# S1-MAIN-20201205.net
KiCad netlist of a schematic drawn in Altium Designer
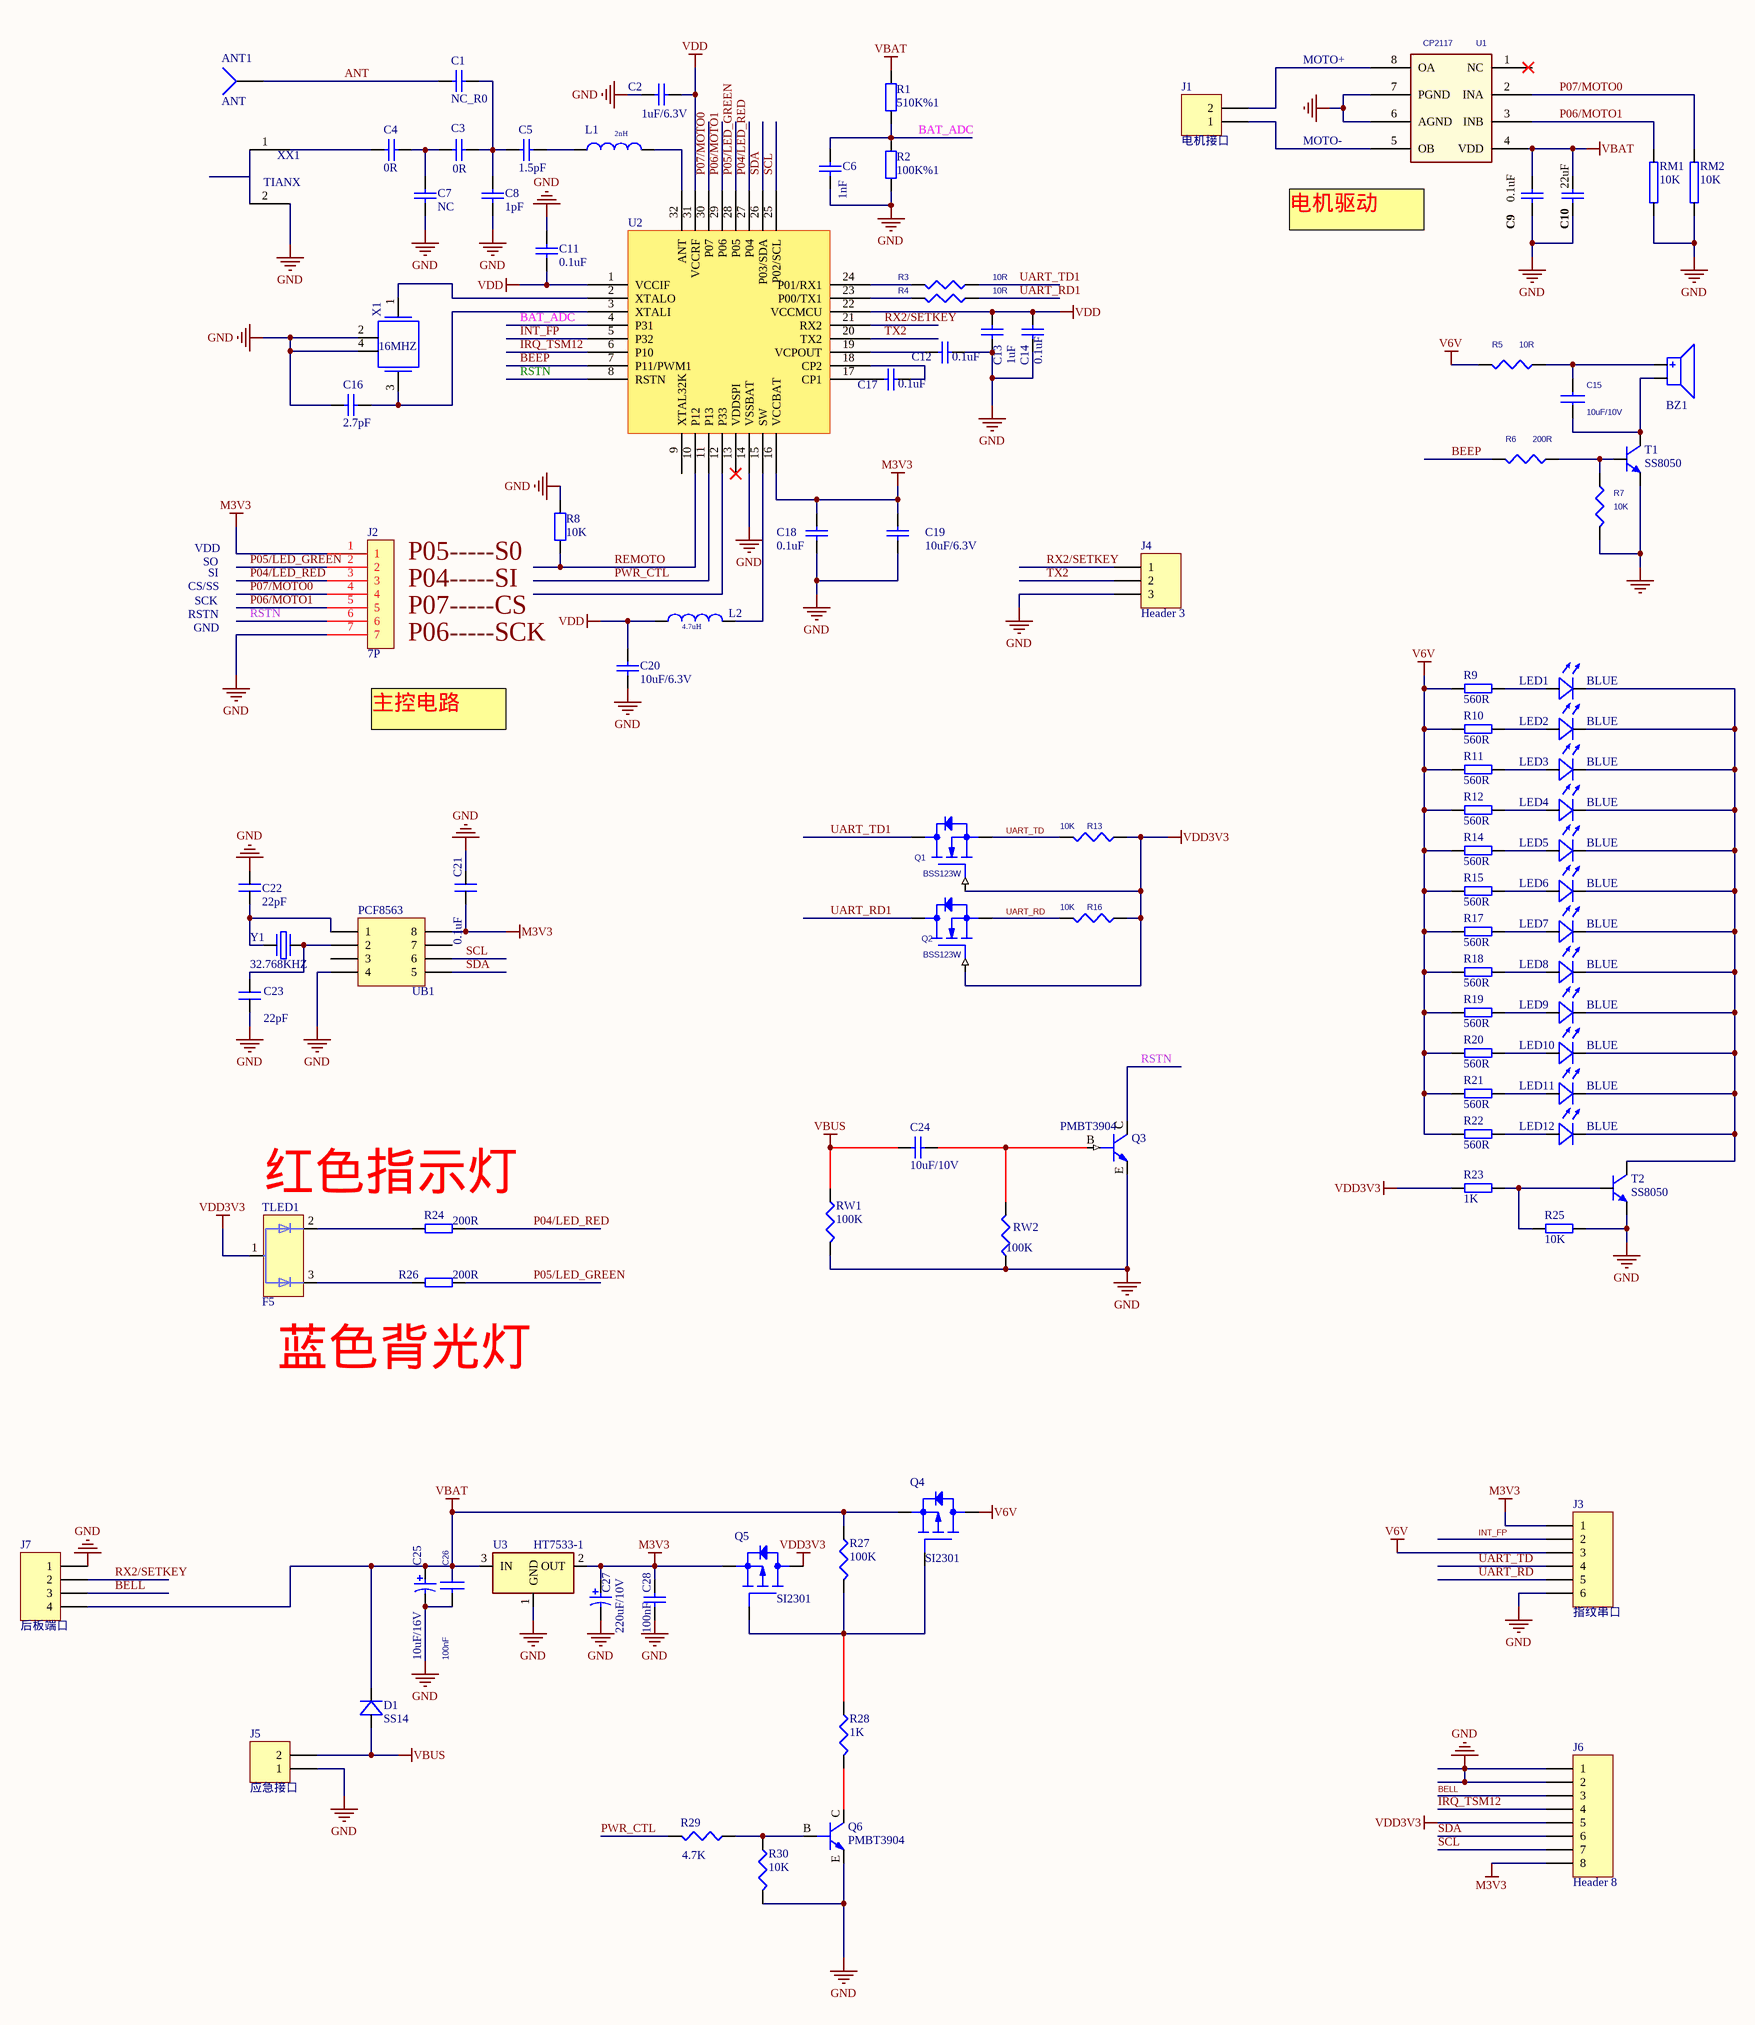
[diagram p0: S1-MAIN-20201205.SchDoc]

(export (version "E")
  (design (tool "Eeschema 10.0.6"))
  (components
    (comp (ref "ANT1")
      (value "ANT")
      (footprint "ANT")
      (description "Socket")
      (fields (field (name "PUBLISHER") "Altium Limited"))
      (libsource (lib "Miscellaneous Connectors") (part "Socket"))
    )
    (comp (ref "BZ1")
      (value "BUZZER")
      (footprint "BUZZER_D93_L40")
      (description "Buzzer")
      (libsource (lib "MyLibrary") (part "BUZZER"))
    )
    (comp (ref "C1")
      (value "NC_R0")
      (footprint "0603C")
      (description "Capacitor")
      (fields (field (name "PUBLISHER") "Altium Limited"))
      (libsource (lib "MySchlib") (part "Cap"))
    )
    (comp (ref "C2")
      (value "1uF/6.3V")
      (footprint "0603C")
      (description "Capacitor")
      (fields (field (name "PUBLISHER") "Altium Limited"))
      (libsource (lib "MySchlib") (part "Cap"))
    )
    (comp (ref "C3")
      (value "0R")
      (footprint "0603C")
      (description "Capacitor")
      (fields (field (name "PUBLISHER") "Altium Limited"))
      (libsource (lib "MySchlib") (part "Cap"))
    )
    (comp (ref "C4")
      (value "0R")
      (footprint "0603C")
      (description "Capacitor")
      (fields (field (name "PUBLISHER") "Altium Limited"))
      (libsource (lib "MySchlib") (part "Cap"))
    )
    (comp (ref "C5")
      (value "1.5pF")
      (footprint "0603C")
      (description "Capacitor")
      (fields (field (name "PUBLISHER") "Altium Limited"))
      (libsource (lib "MySchlib") (part "Cap"))
    )
    (comp (ref "C6")
      (value "1nF")
      (footprint "0603C")
      (description "Capacitor, Ceramic")
      (fields (field (name "TOLERANCE") "5 %"))
      (libsource (lib "MyLibrary") (part "CAP-NP"))
    )
    (comp (ref "C7")
      (value "NC")
      (footprint "0603C")
      (description "Capacitor")
      (fields (field (name "PUBLISHER") "Altium Limited"))
      (libsource (lib "MySchlib") (part "Cap"))
    )
    (comp (ref "C8")
      (value "1pF")
      (footprint "0603C")
      (description "Capacitor")
      (fields (field (name "PUBLISHER") "Altium Limited"))
      (libsource (lib "MySchlib") (part "Cap"))
    )
    (comp (ref "C9")
      (value "0.1uF")
      (footprint "0603C")
      (description "Capacitor, Ceramic")
      (fields (field (name "TOLERANCE") "5 %"))
      (libsource (lib "MyLibrary") (part "CAP-NP"))
    )
    (comp (ref "C10")
      (value "22uF")
      (footprint "0805C")
      (description "Capacitor, Ceramic")
      (fields (field (name "TOLERANCE") "5 %"))
      (libsource (lib "MyLibrary") (part "CAP-NP"))
    )
    (comp (ref "C11")
      (value "0.1uF")
      (footprint "0603C")
      (description "Capacitor")
      (fields (field (name "PUBLISHER") "Altium Limited"))
      (libsource (lib "MySchlib") (part "Cap"))
    )
    (comp (ref "C12")
      (value "0.1uF")
      (footprint "0603C")
      (description "Capacitor")
      (fields (field (name "PUBLISHER") "Altium Limited"))
      (libsource (lib "MySchlib") (part "Cap"))
    )
    (comp (ref "C13")
      (value "1uF")
      (footprint "0603C")
      (description "Capacitor")
      (fields (field (name "PUBLISHER") "Altium Limited"))
      (libsource (lib "MySchlib") (part "Cap"))
    )
    (comp (ref "C14")
      (value "0.1uF")
      (footprint "0603C")
      (description "Capacitor")
      (fields (field (name "PUBLISHER") "Altium Limited"))
      (libsource (lib "MySchlib") (part "Cap"))
    )
    (comp (ref "C15") (value "10uF/10V") (footprint "0603C") (libsource (lib "*") (part "C_0_Dup1")))
    (comp (ref "C16")
      (value "2.7pF")
      (footprint "0603C")
      (description "Capacitor")
      (fields (field (name "PUBLISHER") "Altium Limited"))
      (libsource (lib "MySchlib") (part "Cap"))
    )
    (comp (ref "C17")
      (value "0.1uF")
      (footprint "0603C")
      (description "Capacitor")
      (fields (field (name "PUBLISHER") "Altium Limited"))
      (libsource (lib "MySchlib") (part "Cap"))
    )
    (comp (ref "C18")
      (value "0.1uF")
      (footprint "0603C")
      (description "Capacitor")
      (fields (field (name "PUBLISHER") "Altium Limited"))
      (libsource (lib "MySchlib") (part "Cap"))
    )
    (comp (ref "C19")
      (value "10uF/6.3V")
      (footprint "0603C")
      (description "Capacitor")
      (fields (field (name "PUBLISHER") "Altium Limited"))
      (libsource (lib "MySchlib") (part "Cap"))
    )
    (comp (ref "C20")
      (value "10uF/6.3V")
      (footprint "0603C")
      (description "Capacitor")
      (fields (field (name "PUBLISHER") "Altium Limited"))
      (libsource (lib "MySchlib") (part "Cap"))
    )
    (comp (ref "C21") (value "0.1uF") (footprint "0603C") (libsource (lib "自建元件库") (part "C")))
    (comp (ref "C22") (value "22pF") (footprint "0603C") (libsource (lib "自建元件库") (part "C")))
    (comp (ref "C23") (value "22pF") (footprint "0603C") (libsource (lib "自建元件库") (part "C")))
    (comp (ref "C24")
      (value "10uF/10V")
      (footprint "0603C")
      (description "Capacitor, Ceramic")
      (fields (field (name "TOLERANCE") "5 %"))
      (libsource (lib "MyLibrary") (part "CAP-NP"))
    )
    (comp (ref "C25")
      (value "10uF/16V")
      (footprint "0805C")
      (description "Capacitor, tolerance ±20%")
      (libsource (lib "MySchLib") (part "CAP-P"))
    )
    (comp (ref "C26") (value "100nF") (footprint "0603C") (libsource (lib "*") (part "CAP NP")))
    (comp (ref "C27")
      (value "220uF/10V")
      (footprint "CAP-SMD_6.3*5.8")
      (description "Capacitor, tolerance ±20%")
      (libsource (lib "MySchLib") (part "CAP-P"))
    )
    (comp (ref "C28")
      (value "100nF")
      (footprint "0603C")
      (description "Capacitor, Ceramic")
      (fields (field (name "TOLERANCE") "5 %"))
      (libsource (lib "MyLibrary") (part "CAP-NP"))
    )
    (comp (ref "D1") (value "SS14") (footprint "LC-SMAF_S1") (libsource (lib "MySch") (part "D")))
    (comp (ref "J1")
      (value "电机接口")
      (footprint "S2B-PH-SM3-TB")
      (description "Header, 2-Pin")
      (fields (field (name "PUBLISHER") "Altium Limited"))
      (libsource (lib "Miscellaneous Connectors") (part "MHDR1X2"))
    )
    (comp (ref "J2") (value "7P") (footprint "7P-2.0MM") (libsource (lib "保险箱STM32") (part "7P")))
    (comp (ref "J3")
      (value "指纹串口")
      (footprint "6P-0.5MM_1")
      (description "Header, 6-Pin")
      (fields (field (name "PUBLISHER") "Altium Limited"))
      (libsource (lib "Miscellaneous Connectors") (part "Header 6"))
    )
    (comp (ref "J4")
      (value "Header 3")
      (footprint "3P-2.54MM")
      (description "Header, 3-Pin")
      (fields (field (name "PUBLISHER") "Altium Limited"))
      (libsource (lib "Miscellaneous Connectors") (part "Header 3"))
    )
    (comp (ref "J5")
      (value "应急接口")
      (footprint "2P-1.25mm")
      (description "Header, 2-Pin")
      (fields (field (name "PUBLISHER") "Altium Limited"))
      (libsource (lib "Miscellaneous Connectors") (part "Header 2"))
    )
    (comp (ref "J6")
      (value "Header 8")
      (footprint "8P-1.25MM")
      (description "Header, 8-Pin")
      (fields (field (name "PUBLISHER") "Altium Limited"))
      (libsource (lib "Miscellaneous Connectors") (part "Header 8"))
    )
    (comp (ref "J7")
      (value "后板端口")
      (footprint "JC20-4P")
      (description "Header, 4-Pin, Right Angle")
      (fields (field (name "PUBLISHER") "Altium Limited"))
      (libsource (lib "Miscellaneous Connectors") (part "Header 4H"))
    )
    (comp (ref "L1")
      (value "2nH")
      (footprint "0603L")
      (description "Power Inductor, 4.7uH, 0.7A, 260mR DCR")
      (fields
        (field (name "XMOS PART NUMBER") "E-09-0011")
        (field (name "MANUFACTURER") "Taiyo Yuden")
        (field (name "PART CREATOR") "JG")
        (field (name "APPROVED") "NO")
      )
      (libsource (lib "MySchlib") (part "INDUCTOR"))
    )
    (comp (ref "L2")
      (value "4.7uH")
      (footprint "0805L")
      (description "Power Inductor, 4.7uH, 0.7A, 260mR DCR")
      (fields
        (field (name "XMOS PART NUMBER") "E-09-0011")
        (field (name "MANUFACTURER") "Taiyo Yuden")
        (field (name "PART CREATOR") "JG")
        (field (name "APPROVED") "NO")
      )
      (libsource (lib "MySchlib") (part "INDUCTOR"))
    )
    (comp (ref "LED1") (value "BLUE") (footprint "0603LED") (libsource (lib "MyLibrary") (part "LED")))
    (comp (ref "LED2") (value "BLUE") (footprint "0603LED") (libsource (lib "MyLibrary") (part "LED")))
    (comp (ref "LED3") (value "BLUE") (footprint "0603LED") (libsource (lib "MyLibrary") (part "LED")))
    (comp (ref "LED4") (value "BLUE") (footprint "0603LED") (libsource (lib "MyLibrary") (part "LED")))
    (comp (ref "LED5") (value "BLUE") (footprint "0603LED") (libsource (lib "MyLibrary") (part "LED")))
    (comp (ref "LED6") (value "BLUE") (footprint "0603LED") (libsource (lib "MyLibrary") (part "LED")))
    (comp (ref "LED7") (value "BLUE") (footprint "0603LED") (libsource (lib "MyLibrary") (part "LED")))
    (comp (ref "LED8") (value "BLUE") (footprint "0603LED") (libsource (lib "MyLibrary") (part "LED")))
    (comp (ref "LED9") (value "BLUE") (footprint "0603LED") (libsource (lib "MyLibrary") (part "LED")))
    (comp (ref "LED10") (value "BLUE") (footprint "0603LED") (libsource (lib "MyLibrary") (part "LED")))
    (comp (ref "LED11") (value "BLUE") (footprint "0603LED") (libsource (lib "MyLibrary") (part "LED")))
    (comp (ref "LED12") (value "BLUE") (footprint "0603LED") (libsource (lib "MyLibrary") (part "LED")))
    (comp (ref "Q1") (value "BSS123W") (footprint "SOT-23 - GDS") (libsource (lib "*") (part "BSS123L_0")))
    (comp (ref "Q2") (value "BSS123W") (footprint "SOT-23 - GDS") (libsource (lib "*") (part "BSS123L_0")))
    (comp (ref "Q3") (value "PMBT3904") (footprint "SOT-23 - BCE") (libsource (lib "*") (part "PMBT3904")))
    (comp (ref "Q4")
      (value "SI2301")
      (footprint "SOT-23 - GDS")
      (libsource (lib "*") (part "PWRMOSFET_EP_DGS_0"))
    )
    (comp (ref "Q5")
      (value "SI2301")
      (footprint "SOT-23 - GDS")
      (libsource (lib "*") (part "PWRMOSFET_EP_DGS_0"))
    )
    (comp (ref "Q6") (value "PMBT3904") (footprint "SOT-23 - BCE") (libsource (lib "*") (part "PMBT3904")))
    (comp (ref "R1")
      (value "510K%1")
      (footprint "0603R")
      (description "Resistor")
      (libsource (lib "MyLibrary") (part "Res2"))
    )
    (comp (ref "R2")
      (value "100K%1")
      (footprint "0603R")
      (description "Resistor")
      (libsource (lib "MyLibrary") (part "Res2"))
    )
    (comp (ref "R3") (value "10R") (footprint "0603R") (libsource (lib "*") (part "R_Dup1")))
    (comp (ref "R4") (value "10R") (footprint "0603R") (libsource (lib "*") (part "R_Dup1")))
    (comp (ref "R5") (value "10R") (footprint "0603R") (libsource (lib "*") (part "R_Dup1")))
    (comp (ref "R6") (value "200R") (footprint "0603R") (libsource (lib "*") (part "R_Dup1")))
    (comp (ref "R7") (value "10K") (footprint "0603R") (libsource (lib "*") (part "R_Dup1")))
    (comp (ref "R8")
      (value "10K")
      (footprint "0603R")
      (description "Resistor")
      (libsource (lib "MyLibrary") (part "Res2"))
    )
    (comp (ref "R9") (value "560R") (footprint "0603R") (libsource (lib "MySch") (part "R")))
    (comp (ref "R10") (value "560R") (footprint "0603R") (libsource (lib "MySch") (part "R")))
    (comp (ref "R11") (value "560R") (footprint "0603R") (libsource (lib "MySch") (part "R")))
    (comp (ref "R12") (value "560R") (footprint "0603R") (libsource (lib "MySch") (part "R")))
    (comp (ref "R13") (value "10K") (footprint "0603R") (libsource (lib "*") (part "RES")))
    (comp (ref "R14") (value "560R") (footprint "0603R") (libsource (lib "MySch") (part "R")))
    (comp (ref "R15") (value "560R") (footprint "0603R") (libsource (lib "MySch") (part "R")))
    (comp (ref "R16") (value "10K") (footprint "0603R") (libsource (lib "*") (part "RES")))
    (comp (ref "R17") (value "560R") (footprint "0603R") (libsource (lib "MySch") (part "R")))
    (comp (ref "R18") (value "560R") (footprint "0603R") (libsource (lib "MySch") (part "R")))
    (comp (ref "R19") (value "560R") (footprint "0603R") (libsource (lib "MySch") (part "R")))
    (comp (ref "R20") (value "560R") (footprint "0603R") (libsource (lib "MySch") (part "R")))
    (comp (ref "R21") (value "560R") (footprint "0603R") (libsource (lib "MySch") (part "R")))
    (comp (ref "R22") (value "560R") (footprint "0603R") (libsource (lib "MySch") (part "R")))
    (comp (ref "R23") (value "1K") (footprint "0603R") (libsource (lib "MySch") (part "R")))
    (comp (ref "R24") (value "200R") (footprint "LC-0603_R") (libsource (lib "MySch") (part "R")))
    (comp (ref "R25") (value "10K") (footprint "0603R") (libsource (lib "MySch") (part "R")))
    (comp (ref "R26") (value "200R") (footprint "LC-0603_R") (libsource (lib "MySch") (part "R")))
    (comp (ref "R27") (value "100K") (footprint "LC-0603_R") (libsource (lib "*") (part "R")))
    (comp (ref "R28") (value "1K") (footprint "LC-0603_R") (libsource (lib "*") (part "R")))
    (comp (ref "R29") (value "4.7K") (footprint "LC-0603_R") (libsource (lib "*") (part "R")))
    (comp (ref "R30") (value "10K") (footprint "LC-0603_R") (libsource (lib "*") (part "R")))
    (comp (ref "RM1") (value "10K") (footprint "0603R") (libsource (lib "*") (part "Pro71C3.TMP_UnNamed_1")))
    (comp (ref "RM2") (value "10K") (footprint "0603R") (libsource (lib "*") (part "Pro71C3.TMP_UnNamed_1")))
    (comp (ref "RW1") (value "100K") (footprint "LC-0603_R") (libsource (lib "*") (part "R")))
    (comp (ref "RW2") (value "100K") (footprint "LC-0603_R") (libsource (lib "*") (part "R")))
    (comp (ref "T1")
      (value "SS8050")
      (footprint "SOT-23-3L")
      (description "Bipolar Junction Transistor")
      (libsource (lib "MyLibrary") (part "NPN_BJT"))
    )
    (comp (ref "T2")
      (value "SS8050")
      (footprint "SOT-23-3L")
      (description "Bipolar Junction Transistor")
      (libsource (lib "MyLibrary") (part "NPN_BJT"))
    )
    (comp (ref "TLED1") (value "F5") (footprint "F5_DIP2") (libsource (lib "Schlib1") (part "WWXMFGLY")))
    (comp (ref "U1") (value "CP2117") (footprint "SOP8") (libsource (lib "*") (part "AM24LC02_0")))
    (comp (ref "U2")
      (value "BK3431Q")
      (footprint "QFN32_4*4*0.4")
      (libsource (lib "BK3431") (part "BK3431Q"))
    )
    (comp (ref "U3") (value "HT7533-1") (footprint "SOT-23-3L") (libsource (lib "*") (part "XC6206P302M")))
    (comp (ref "UB1") (value "PCF8563") (footprint "SOP8") (libsource (lib "MySch") (part "IC8")))
    (comp (ref "X1")
      (value "16MHZ")
      (footprint "XTAL3225")
      (fields
        (field (name "XMOS PART NUMBER") "E-07-0030")
        (field (name "MANUFACTURER") "Abracon")
        (field (name "MANUFACTURER PART NUMBER") "ABLS-24.000MHz-B4")
        (field (name "PART CREATOR") "JG")
        (field (name "APPROVED") "NO")
      )
      (libsource (lib "MySchlib") (part "OSC"))
    )
    (comp (ref "XX1")
      (value "TIANX")
      (footprint "BT_NAMI")
      (libsource (lib "885阿里云PCB_Project1") (part "TIANX"))
    )
    (comp (ref "Y1") (value "32.768KHZ") (footprint "晶振-9") (libsource (lib "MySch") (part "晶振")))
  )
  (nets
    (net (code "1") (name "/ANT") (class "Default")
      (node (ref "ANT1") (pin "1") (pinfunction "1_1") (pintype "passive"))
      (node (ref "C1") (pin "1") (pinfunction "1_1") (pintype "passive"))
    )
    (net (code "2") (name "/BAT_ADC") (class "Default")
      (node (ref "C6") (pin "2") (pinfunction "2_2") (pintype "passive"))
      (node (ref "R1") (pin "2") (pinfunction "2_2") (pintype "passive"))
      (node (ref "R2") (pin "1") (pinfunction "1_1") (pintype "passive"))
      (node (ref "U2") (pin "4") (pinfunction "P31_4") (pintype "passive"))
    )
    (net (code "3") (name "/BEEP") (class "Default")
      (node (ref "R6") (pin "2") (pinfunction "2_2") (pintype "passive"))
      (node (ref "U2") (pin "7") (pinfunction "P11/PWM1_7") (pintype "passive"))
    )
    (net (code "4") (name "/BELL") (class "Default")
      (node (ref "J6") (pin "3") (pinfunction "3_3") (pintype "passive"))
      (node (ref "J7") (pin "3") (pinfunction "3_3") (pintype "passive"))
    )
    (net (code "5") (name "/INT_FP") (class "Default")
      (node (ref "J3") (pin "2") (pinfunction "2_2") (pintype "passive"))
      (node (ref "U2") (pin "5") (pinfunction "P32_5") (pintype "passive"))
    )
    (net (code "6") (name "/IRQ_TSM12") (class "Default")
      (node (ref "J6") (pin "4") (pinfunction "4_4") (pintype "passive"))
      (node (ref "U2") (pin "6") (pinfunction "P10_6") (pintype "passive"))
    )
    (net (code "7") (name "/P04{slash}LED_RED") (class "Default")
      (node (ref "J2") (pin "3") (pinfunction "3_3") (pintype "passive"))
      (node (ref "R24") (pin "2") (pintype "passive"))
      (node (ref "U2") (pin "27") (pinfunction "P04_27") (pintype "passive"))
    )
    (net (code "8") (name "/P05{slash}LED_GREEN") (class "Default")
      (node (ref "J2") (pin "2") (pinfunction "2_2") (pintype "passive"))
      (node (ref "R26") (pin "2") (pintype "passive"))
      (node (ref "U2") (pin "28") (pinfunction "P05_28") (pintype "passive"))
    )
    (net (code "9") (name "/P06{slash}MOTO1") (class "Default")
      (node (ref "J2") (pin "5") (pinfunction "5_5") (pintype "passive"))
      (node (ref "RM1") (pin "2") (pintype "passive"))
      (node (ref "U1") (pin "3") (pinfunction "INB_3") (pintype "passive"))
      (node (ref "U2") (pin "29") (pinfunction "P06_29") (pintype "passive"))
    )
    (net (code "10") (name "/P07{slash}MOTO0") (class "Default")
      (node (ref "J2") (pin "4") (pinfunction "4_4") (pintype "passive"))
      (node (ref "RM2") (pin "2") (pintype "passive"))
      (node (ref "U1") (pin "2") (pinfunction "INA_2") (pintype "passive"))
      (node (ref "U2") (pin "30") (pinfunction "P07_30") (pintype "passive"))
    )
    (net (code "11") (name "/PWR_CTL") (class "Default")
      (node (ref "R29") (pin "2") (pinfunction "2_2") (pintype "passive"))
      (node (ref "U2") (pin "11") (pinfunction "P13_11") (pintype "passive"))
    )
    (net (code "12") (name "/REMOTO") (class "Default")
      (node (ref "R8") (pin "2") (pinfunction "2_2") (pintype "passive"))
      (node (ref "U2") (pin "10") (pinfunction "P12_10") (pintype "passive"))
    )
    (net (code "13") (name "/RSTN") (class "Default")
      (node (ref "J2") (pin "6") (pinfunction "6_6") (pintype "passive"))
      (node (ref "Q3") (pin "C") (pinfunction "COLLECTOR_C") (pintype "passive"))
      (node (ref "U2") (pin "8") (pinfunction "RSTN_8") (pintype "passive"))
    )
    (net (code "14") (name "/RX2{slash}SETKEY") (class "Default")
      (node (ref "J4") (pin "1") (pinfunction "1_1") (pintype "passive"))
      (node (ref "J7") (pin "2") (pinfunction "2_2") (pintype "passive"))
      (node (ref "U2") (pin "21") (pinfunction "RX2_21") (pintype "passive"))
    )
    (net (code "15") (name "/SCL") (class "Default")
      (node (ref "J6") (pin "7") (pinfunction "7_7") (pintype "passive"))
      (node (ref "U2") (pin "25") (pinfunction "P02/SCL_25") (pintype "passive"))
      (node (ref "UB1") (pin "6") (pinfunction "6_6") (pintype "passive"))
    )
    (net (code "16") (name "/SDA") (class "Default")
      (node (ref "J6") (pin "6") (pinfunction "6_6") (pintype "passive"))
      (node (ref "U2") (pin "26") (pinfunction "P03/SDA_26") (pintype "passive"))
      (node (ref "UB1") (pin "5") (pinfunction "5_5") (pintype "passive"))
    )
    (net (code "17") (name "/TX2") (class "Default")
      (node (ref "J4") (pin "2") (pinfunction "2_2") (pintype "passive"))
      (node (ref "U2") (pin "20") (pinfunction "TX2_20") (pintype "passive"))
    )
    (net (code "18") (name "/UART_RD") (class "Default")
      (node (ref "J3") (pin "5") (pinfunction "5_5") (pintype "passive"))
      (node (ref "Q2") (pin "S") (pinfunction "SOURCE_S") (pintype "passive"))
      (node (ref "R16") (pin "1") (pinfunction "1_1") (pintype "passive"))
    )
    (net (code "19") (name "/UART_RD1") (class "Default")
      (node (ref "Q2") (pin "D") (pinfunction "DRAIN_D") (pintype "passive"))
      (node (ref "R4") (pin "1") (pinfunction "1_1") (pintype "passive"))
    )
    (net (code "20") (name "/UART_TD") (class "Default")
      (node (ref "J3") (pin "4") (pinfunction "4_4") (pintype "passive"))
      (node (ref "Q1") (pin "S") (pinfunction "SOURCE_S") (pintype "passive"))
      (node (ref "R13") (pin "1") (pinfunction "1_1") (pintype "passive"))
    )
    (net (code "21") (name "/UART_TD1") (class "Default")
      (node (ref "Q1") (pin "D") (pinfunction "DRAIN_D") (pintype "passive"))
      (node (ref "R3") (pin "1") (pinfunction "1_1") (pintype "passive"))
    )
    (net (code "22") (name "GND") (class "Default")
      (node (ref "C10") (pin "2") (pinfunction "2_2") (pintype "passive"))
      (node (ref "C11") (pin "1") (pinfunction "1_1") (pintype "passive"))
      (node (ref "C12") (pin "2") (pinfunction "2_2") (pintype "passive"))
      (node (ref "C13") (pin "1") (pinfunction "1_1") (pintype "passive"))
      (node (ref "C14") (pin "1") (pinfunction "1_1") (pintype "passive"))
      (node (ref "C16") (pin "1") (pinfunction "1_1") (pintype "passive"))
      (node (ref "C18") (pin "2") (pinfunction "2_2") (pintype "passive"))
      (node (ref "C19") (pin "2") (pinfunction "2_2") (pintype "passive"))
      (node (ref "C2") (pin "1") (pinfunction "1_1") (pintype "passive"))
      (node (ref "C20") (pin "1") (pinfunction "1_1") (pintype "passive"))
      (node (ref "C21") (pin "2") (pintype "passive"))
      (node (ref "C22") (pin "2") (pintype "passive"))
      (node (ref "C23") (pin "1") (pintype "passive"))
      (node (ref "C25") (pin "2") (pinfunction "2_2") (pintype "passive"))
      (node (ref "C26") (pin "2") (pinfunction "2_2") (pintype "passive"))
      (node (ref "C27") (pin "2") (pinfunction "2_2") (pintype "passive"))
      (node (ref "C28") (pin "2") (pinfunction "2_2") (pintype "passive"))
      (node (ref "C6") (pin "1") (pinfunction "1_1") (pintype "passive"))
      (node (ref "C7") (pin "2") (pinfunction "2_2") (pintype "passive"))
      (node (ref "C8") (pin "1") (pinfunction "1_1") (pintype "passive"))
      (node (ref "C9") (pin "2") (pinfunction "2_2") (pintype "passive"))
      (node (ref "J2") (pin "7") (pinfunction "7_7") (pintype "passive"))
      (node (ref "J3") (pin "6") (pinfunction "6_6") (pintype "passive"))
      (node (ref "J4") (pin "3") (pinfunction "3_3") (pintype "passive"))
      (node (ref "J5") (pin "1") (pinfunction "1_1") (pintype "passive"))
      (node (ref "J6") (pin "1") (pinfunction "1_1") (pintype "passive"))
      (node (ref "J6") (pin "2") (pinfunction "2_2") (pintype "passive"))
      (node (ref "J7") (pin "1") (pinfunction "1_1") (pintype "passive"))
      (node (ref "Q3") (pin "E") (pinfunction "EMITTER_E") (pintype "passive"))
      (node (ref "Q6") (pin "E") (pinfunction "EMITTER_E") (pintype "passive"))
      (node (ref "R2") (pin "2") (pinfunction "2_2") (pintype "passive"))
      (node (ref "R25") (pin "1") (pintype "passive"))
      (node (ref "R30") (pin "2") (pinfunction "2_2") (pintype "passive"))
      (node (ref "R7") (pin "2") (pinfunction "2_2") (pintype "passive"))
      (node (ref "R8") (pin "1") (pinfunction "1_1") (pintype "passive"))
      (node (ref "RM1") (pin "1") (pintype "passive"))
      (node (ref "RM2") (pin "1") (pintype "passive"))
      (node (ref "RW1") (pin "2") (pinfunction "2_2") (pintype "passive"))
      (node (ref "RW2") (pin "1") (pinfunction "1_1") (pintype "passive"))
      (node (ref "T1") (pin "2") (pinfunction "2_2") (pintype "passive"))
      (node (ref "T2") (pin "2") (pinfunction "2_2") (pintype "passive"))
      (node (ref "U1") (pin "6") (pinfunction "AGND_6") (pintype "passive"))
      (node (ref "U1") (pin "7") (pinfunction "PGND_7") (pintype "passive"))
      (node (ref "U2") (pin "14") (pinfunction "VSSBAT_14") (pintype "passive"))
      (node (ref "U3") (pin "1") (pinfunction "GND_1") (pintype "passive"))
      (node (ref "UB1") (pin "4") (pinfunction "4_4") (pintype "passive"))
      (node (ref "X1") (pin "2") (pintype "passive"))
      (node (ref "X1") (pin "4") (pintype "passive"))
      (node (ref "XX1") (pin "2") (pinfunction "2_2") (pintype "passive"))
    )
    (net (code "23") (name "M3V3") (class "Default")
      (node (ref "C18") (pin "1") (pinfunction "1_1") (pintype "passive"))
      (node (ref "C19") (pin "1") (pinfunction "1_1") (pintype "passive"))
      (node (ref "C21") (pin "1") (pintype "passive"))
      (node (ref "C27") (pin "1") (pinfunction "1_1") (pintype "passive"))
      (node (ref "C28") (pin "1") (pinfunction "1_1") (pintype "passive"))
      (node (ref "J2") (pin "1") (pinfunction "1_1") (pintype "passive"))
      (node (ref "J3") (pin "1") (pinfunction "1_1") (pintype "passive"))
      (node (ref "J6") (pin "8") (pinfunction "8_8") (pintype "passive"))
      (node (ref "Q5") (pin "S") (pinfunction "SOURCE_S") (pintype "passive"))
      (node (ref "U2") (pin "16") (pinfunction "VCCBAT_16") (pintype "passive"))
      (node (ref "U3") (pin "2") (pinfunction "OUT_2") (pintype "passive"))
      (node (ref "UB1") (pin "8") (pinfunction "8_8") (pintype "passive"))
    )
    (net (code "24") (name "Net-(BZ1-Pad1)") (class "Default")
      (node (ref "BZ1") (pin "1") (pintype "passive"))
      (node (ref "C15") (pin "2") (pinfunction "2_2") (pintype "passive"))
      (node (ref "R5") (pin "1") (pinfunction "1_1") (pintype "passive"))
    )
    (net (code "25") (name "Net-(BZ1-Pad2)") (class "Default")
      (node (ref "BZ1") (pin "2") (pintype "passive"))
      (node (ref "C15") (pin "1") (pinfunction "1_1") (pintype "passive"))
      (node (ref "T1") (pin "3") (pinfunction "3_3") (pintype "passive"))
    )
    (net (code "26") (name "Net-(C1-Pad2)") (class "Default")
      (node (ref "C1") (pin "2") (pinfunction "2_2") (pintype "passive"))
      (node (ref "C3") (pin "2") (pinfunction "2_2") (pintype "passive"))
      (node (ref "C5") (pin "2") (pinfunction "2_2") (pintype "passive"))
      (node (ref "C8") (pin "2") (pinfunction "2_2") (pintype "passive"))
    )
    (net (code "27") (name "Net-(C3-Pad1)") (class "Default")
      (node (ref "C3") (pin "1") (pinfunction "1_1") (pintype "passive"))
      (node (ref "C4") (pin "2") (pinfunction "2_2") (pintype "passive"))
      (node (ref "C7") (pin "1") (pinfunction "1_1") (pintype "passive"))
    )
    (net (code "28") (name "Net-(C4-Pad1)") (class "Default")
      (node (ref "C4") (pin "1") (pinfunction "1_1") (pintype "passive"))
      (node (ref "XX1") (pin "1") (pinfunction "1_1") (pintype "passive"))
    )
    (net (code "29") (name "Net-(C22-Pad1)") (class "Default")
      (node (ref "C22") (pin "1") (pintype "passive"))
      (node (ref "UB1") (pin "1") (pinfunction "1_1") (pintype "passive"))
      (node (ref "Y1") (pin "2") (pintype "passive"))
    )
    (net (code "30") (name "Net-(C23-Pad2)") (class "Default")
      (node (ref "C23") (pin "2") (pintype "passive"))
      (node (ref "UB1") (pin "2") (pinfunction "2_2") (pintype "passive"))
      (node (ref "Y1") (pin "1") (pintype "passive"))
    )
    (net (code "31") (name "Net-(L1-P1)") (class "Default")
      (node (ref "C5") (pin "1") (pinfunction "1_1") (pintype "passive"))
      (node (ref "L1") (pin "1") (pinfunction "P1_1") (pintype "passive"))
    )
    (net (code "32") (name "Net-(L1-P2)") (class "Default")
      (node (ref "L1") (pin "2") (pinfunction "P2_2") (pintype "passive"))
      (node (ref "U2") (pin "32") (pinfunction "ANT_32") (pintype "passive"))
    )
    (net (code "33") (name "Net-(L2-P2)") (class "Default")
      (node (ref "L2") (pin "2") (pinfunction "P2_2") (pintype "passive"))
      (node (ref "U2") (pin "15") (pinfunction "SW_15") (pintype "passive"))
    )
    (net (code "34") (name "Net-(LED1-A)") (class "Default")
      (node (ref "LED1") (pin "1") (pinfunction "A_1") (pintype "passive"))
      (node (ref "R9") (pin "2") (pintype "passive"))
    )
    (net (code "35") (name "Net-(LED1-K)") (class "Default")
      (node (ref "LED1") (pin "2") (pinfunction "K_2") (pintype "passive"))
      (node (ref "LED10") (pin "2") (pinfunction "K_2") (pintype "passive"))
      (node (ref "LED11") (pin "2") (pinfunction "K_2") (pintype "passive"))
      (node (ref "LED12") (pin "2") (pinfunction "K_2") (pintype "passive"))
      (node (ref "LED2") (pin "2") (pinfunction "K_2") (pintype "passive"))
      (node (ref "LED3") (pin "2") (pinfunction "K_2") (pintype "passive"))
      (node (ref "LED4") (pin "2") (pinfunction "K_2") (pintype "passive"))
      (node (ref "LED5") (pin "2") (pinfunction "K_2") (pintype "passive"))
      (node (ref "LED6") (pin "2") (pinfunction "K_2") (pintype "passive"))
      (node (ref "LED7") (pin "2") (pinfunction "K_2") (pintype "passive"))
      (node (ref "LED8") (pin "2") (pinfunction "K_2") (pintype "passive"))
      (node (ref "LED9") (pin "2") (pinfunction "K_2") (pintype "passive"))
      (node (ref "T2") (pin "3") (pinfunction "3_3") (pintype "passive"))
    )
    (net (code "36") (name "Net-(LED2-A)") (class "Default")
      (node (ref "LED2") (pin "1") (pinfunction "A_1") (pintype "passive"))
      (node (ref "R10") (pin "2") (pintype "passive"))
    )
    (net (code "37") (name "Net-(LED3-A)") (class "Default")
      (node (ref "LED3") (pin "1") (pinfunction "A_1") (pintype "passive"))
      (node (ref "R11") (pin "2") (pintype "passive"))
    )
    (net (code "38") (name "Net-(LED4-A)") (class "Default")
      (node (ref "LED4") (pin "1") (pinfunction "A_1") (pintype "passive"))
      (node (ref "R12") (pin "2") (pintype "passive"))
    )
    (net (code "39") (name "Net-(LED5-A)") (class "Default")
      (node (ref "LED5") (pin "1") (pinfunction "A_1") (pintype "passive"))
      (node (ref "R14") (pin "2") (pintype "passive"))
    )
    (net (code "40") (name "Net-(LED6-A)") (class "Default")
      (node (ref "LED6") (pin "1") (pinfunction "A_1") (pintype "passive"))
      (node (ref "R15") (pin "2") (pintype "passive"))
    )
    (net (code "41") (name "Net-(LED7-A)") (class "Default")
      (node (ref "LED7") (pin "1") (pinfunction "A_1") (pintype "passive"))
      (node (ref "R17") (pin "2") (pintype "passive"))
    )
    (net (code "42") (name "Net-(LED8-A)") (class "Default")
      (node (ref "LED8") (pin "1") (pinfunction "A_1") (pintype "passive"))
      (node (ref "R18") (pin "2") (pintype "passive"))
    )
    (net (code "43") (name "Net-(LED9-A)") (class "Default")
      (node (ref "LED9") (pin "1") (pinfunction "A_1") (pintype "passive"))
      (node (ref "R19") (pin "2") (pintype "passive"))
    )
    (net (code "44") (name "Net-(LED10-A)") (class "Default")
      (node (ref "LED10") (pin "1") (pinfunction "A_1") (pintype "passive"))
      (node (ref "R20") (pin "2") (pintype "passive"))
    )
    (net (code "45") (name "Net-(LED11-A)") (class "Default")
      (node (ref "LED11") (pin "1") (pinfunction "A_1") (pintype "passive"))
      (node (ref "R21") (pin "2") (pintype "passive"))
    )
    (net (code "46") (name "Net-(LED12-A)") (class "Default")
      (node (ref "LED12") (pin "1") (pinfunction "A_1") (pintype "passive"))
      (node (ref "R22") (pin "2") (pintype "passive"))
    )
    (net (code "47") (name "Net-(Q3-BASE)") (class "Default")
      (node (ref "C24") (pin "2") (pinfunction "2_2") (pintype "passive"))
      (node (ref "Q3") (pin "B") (pinfunction "BASE_B") (pintype "passive"))
      (node (ref "RW2") (pin "2") (pinfunction "2_2") (pintype "passive"))
    )
    (net (code "48") (name "Net-(Q4-GATE)") (class "Default")
      (node (ref "Q4") (pin "G") (pinfunction "GATE_G") (pintype "passive"))
      (node (ref "Q5") (pin "G") (pinfunction "GATE_G") (pintype "passive"))
      (node (ref "R27") (pin "2") (pinfunction "2_2") (pintype "passive"))
      (node (ref "R28") (pin "1") (pinfunction "1_1") (pintype "passive"))
    )
    (net (code "49") (name "Net-(Q6-BASE)") (class "Default")
      (node (ref "Q6") (pin "B") (pinfunction "BASE_B") (pintype "passive"))
      (node (ref "R29") (pin "1") (pinfunction "1_1") (pintype "passive"))
      (node (ref "R30") (pin "1") (pinfunction "1_1") (pintype "passive"))
    )
    (net (code "50") (name "Net-(Q6-COLLECTOR)") (class "Default")
      (node (ref "Q6") (pin "C") (pinfunction "COLLECTOR_C") (pintype "passive"))
      (node (ref "R28") (pin "2") (pinfunction "2_2") (pintype "passive"))
    )
    (net (code "51") (name "Net-(R6-Pad1)") (class "Default")
      (node (ref "R6") (pin "1") (pinfunction "1_1") (pintype "passive"))
      (node (ref "R7") (pin "1") (pinfunction "1_1") (pintype "passive"))
      (node (ref "T1") (pin "1") (pinfunction "1_1") (pintype "passive"))
    )
    (net (code "52") (name "Net-(R23-Pad2)") (class "Default")
      (node (ref "R23") (pin "2") (pintype "passive"))
      (node (ref "R25") (pin "2") (pintype "passive"))
      (node (ref "T2") (pin "1") (pinfunction "1_1") (pintype "passive"))
    )
    (net (code "53") (name "Net-(TLED1-GK)") (class "Default")
      (node (ref "R26") (pin "1") (pintype "passive"))
      (node (ref "TLED1") (pin "3") (pinfunction "GK_3") (pintype "passive"))
    )
    (net (code "54") (name "Net-(TLED1-RK)") (class "Default")
      (node (ref "R24") (pin "1") (pintype "passive"))
      (node (ref "TLED1") (pin "2") (pinfunction "RK_2") (pintype "passive"))
    )
    (net (code "55") (name "Net-(U1-OA)") (class "Default")
      (node (ref "J1") (pin "2") (pinfunction "2_2") (pintype "passive"))
      (node (ref "U1") (pin "8") (pinfunction "OA_8") (pintype "passive"))
    )
    (net (code "56") (name "Net-(U1-OB)") (class "Default")
      (node (ref "J1") (pin "1") (pinfunction "1_1") (pintype "passive"))
      (node (ref "U1") (pin "5") (pinfunction "OB_5") (pintype "passive"))
    )
    (net (code "57") (name "Net-(U2-CP1)") (class "Default")
      (node (ref "C17") (pin "1") (pinfunction "1_1") (pintype "passive"))
      (node (ref "U2") (pin "17") (pinfunction "CP1_17") (pintype "passive"))
    )
    (net (code "58") (name "Net-(U2-CP2)") (class "Default")
      (node (ref "C17") (pin "2") (pinfunction "2_2") (pintype "passive"))
      (node (ref "U2") (pin "18") (pinfunction "CP2_18") (pintype "passive"))
    )
    (net (code "59") (name "Net-(U2-P00{slash}TX1)") (class "Default")
      (node (ref "R4") (pin "2") (pinfunction "2_2") (pintype "passive"))
      (node (ref "U2") (pin "23") (pinfunction "P00/TX1_23") (pintype "passive"))
    )
    (net (code "60") (name "Net-(U2-P01{slash}RX1)") (class "Default")
      (node (ref "R3") (pin "2") (pinfunction "2_2") (pintype "passive"))
      (node (ref "U2") (pin "24") (pinfunction "P01/RX1_24") (pintype "passive"))
    )
    (net (code "61") (name "Net-(U2-VCPOUT)") (class "Default")
      (node (ref "C12") (pin "1") (pinfunction "1_1") (pintype "passive"))
      (node (ref "U2") (pin "19") (pinfunction "VCPOUT_19") (pintype "passive"))
    )
    (net (code "62") (name "Net-(U2-XTALI)") (class "Default")
      (node (ref "C16") (pin "2") (pinfunction "2_2") (pintype "passive"))
      (node (ref "U2") (pin "3") (pinfunction "XTALI_3") (pintype "passive"))
      (node (ref "X1") (pin "3") (pintype "passive"))
    )
    (net (code "63") (name "Net-(U2-XTALO)") (class "Default")
      (node (ref "U2") (pin "2") (pinfunction "XTALO_2") (pintype "passive"))
      (node (ref "X1") (pin "1") (pintype "passive"))
    )
    (net (code "64") (name "V6V") (class "Default")
      (node (ref "J3") (pin "3") (pinfunction "3_3") (pintype "passive"))
      (node (ref "Q4") (pin "D") (pinfunction "DRAIN_D") (pintype "passive"))
      (node (ref "R10") (pin "1") (pintype "passive"))
      (node (ref "R11") (pin "1") (pintype "passive"))
      (node (ref "R12") (pin "1") (pintype "passive"))
      (node (ref "R14") (pin "1") (pintype "passive"))
      (node (ref "R15") (pin "1") (pintype "passive"))
      (node (ref "R17") (pin "1") (pintype "passive"))
      (node (ref "R18") (pin "1") (pintype "passive"))
      (node (ref "R19") (pin "1") (pintype "passive"))
      (node (ref "R20") (pin "1") (pintype "passive"))
      (node (ref "R21") (pin "1") (pintype "passive"))
      (node (ref "R22") (pin "1") (pintype "passive"))
      (node (ref "R5") (pin "2") (pinfunction "2_2") (pintype "passive"))
      (node (ref "R9") (pin "1") (pintype "passive"))
    )
    (net (code "65") (name "VBAT") (class "Default")
      (node (ref "C10") (pin "1") (pinfunction "1_1") (pintype "passive"))
      (node (ref "C25") (pin "1") (pinfunction "1_1") (pintype "passive"))
      (node (ref "C26") (pin "1") (pinfunction "1_1") (pintype "passive"))
      (node (ref "C9") (pin "1") (pinfunction "1_1") (pintype "passive"))
      (node (ref "D1") (pin "2") (pinfunction "K_2") (pintype "passive"))
      (node (ref "J7") (pin "4") (pinfunction "4_4") (pintype "passive"))
      (node (ref "Q4") (pin "S") (pinfunction "SOURCE_S") (pintype "passive"))
      (node (ref "R1") (pin "1") (pinfunction "1_1") (pintype "passive"))
      (node (ref "R27") (pin "1") (pinfunction "1_1") (pintype "passive"))
      (node (ref "U1") (pin "4") (pinfunction "VDD_4") (pintype "passive"))
      (node (ref "U3") (pin "3") (pinfunction "IN_3") (pintype "passive"))
    )
    (net (code "66") (name "VBUS") (class "Default")
      (node (ref "C24") (pin "1") (pinfunction "1_1") (pintype "passive"))
      (node (ref "D1") (pin "1") (pinfunction "A_1") (pintype "passive"))
      (node (ref "J5") (pin "2") (pinfunction "2_2") (pintype "passive"))
      (node (ref "RW1") (pin "1") (pinfunction "1_1") (pintype "passive"))
    )
    (net (code "67") (name "VDD") (class "Default")
      (node (ref "C11") (pin "2") (pinfunction "2_2") (pintype "passive"))
      (node (ref "C13") (pin "2") (pinfunction "2_2") (pintype "passive"))
      (node (ref "C14") (pin "2") (pinfunction "2_2") (pintype "passive"))
      (node (ref "C2") (pin "2") (pinfunction "2_2") (pintype "passive"))
      (node (ref "C20") (pin "2") (pinfunction "2_2") (pintype "passive"))
      (node (ref "L2") (pin "1") (pinfunction "P1_1") (pintype "passive"))
      (node (ref "U2") (pin "1") (pinfunction "VCCIF_1") (pintype "passive"))
      (node (ref "U2") (pin "22") (pinfunction "VCCMCU_22") (pintype "passive"))
      (node (ref "U2") (pin "31") (pinfunction "VCCRF_31") (pintype "passive"))
    )
    (net (code "68") (name "VDD3V3") (class "Default")
      (node (ref "J6") (pin "5") (pinfunction "5_5") (pintype "passive"))
      (node (ref "Q1") (pin "G") (pinfunction "GATE_G") (pintype "input"))
      (node (ref "Q2") (pin "G") (pinfunction "GATE_G") (pintype "input"))
      (node (ref "Q5") (pin "D") (pinfunction "DRAIN_D") (pintype "passive"))
      (node (ref "R13") (pin "2") (pinfunction "2_2") (pintype "passive"))
      (node (ref "R16") (pin "2") (pinfunction "2_2") (pintype "passive"))
      (node (ref "R23") (pin "1") (pintype "passive"))
      (node (ref "TLED1") (pin "1") (pinfunction "A_1") (pintype "passive"))
    )
    (net (code "69") (name "unconnected-(U1-NC-Pad1)") (class "Default")
      (node (ref "U1") (pin "1") (pinfunction "NC_1") (pintype "passive"))
    )
    (net (code "70") (name "unconnected-(U2-P33-Pad12)") (class "Default")
      (node (ref "U2") (pin "12") (pinfunction "P33_12") (pintype "passive"))
    )
    (net (code "71") (name "unconnected-(U2-VDDSPI-Pad13)") (class "Default")
      (node (ref "U2") (pin "13") (pinfunction "VDDSPI_13") (pintype "passive+no_connect"))
    )
    (net (code "72") (name "unconnected-(U2-XTAL32K-Pad9)") (class "Default")
      (node (ref "U2") (pin "9") (pinfunction "XTAL32K_9") (pintype "passive"))
    )
    (net (code "73") (name "unconnected-(UB1-Pad3)") (class "Default")
      (node (ref "UB1") (pin "3") (pinfunction "3_3") (pintype "passive"))
    )
    (net (code "74") (name "unconnected-(UB1-Pad7)") (class "Default")
      (node (ref "UB1") (pin "7") (pinfunction "7_7") (pintype "passive"))
    )
  )
)
